# encoder-hbridge.net
KiCad netlist of a schematic drawn in EAGLE
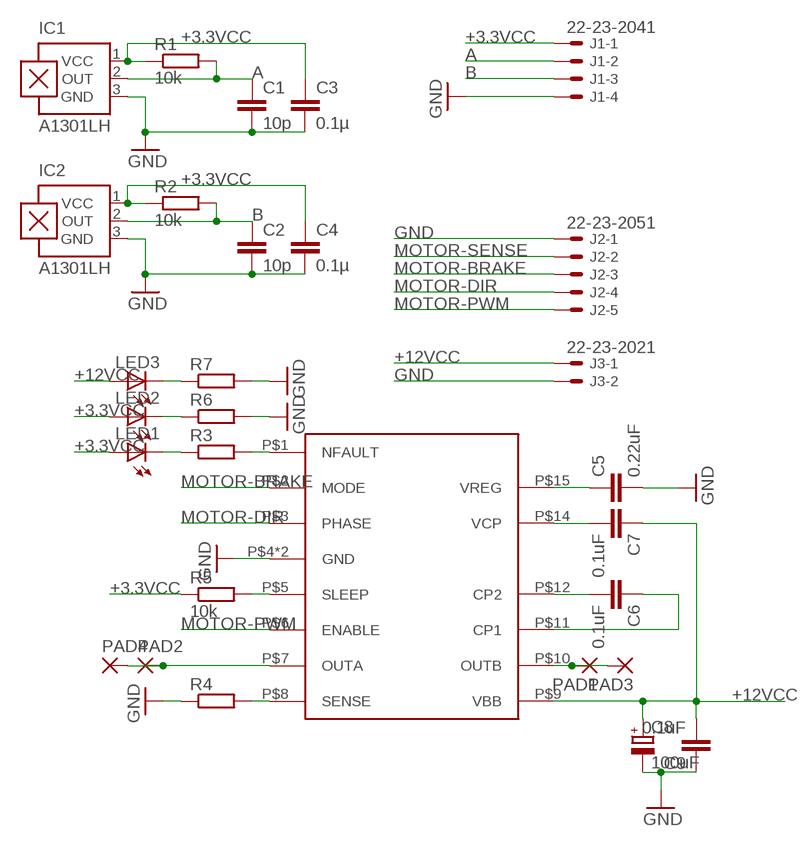
[diagram p0: schematic, sheet 1]

(export (version "E")
  (design (tool "Eeschema 10.0.6"))
  (components
    (comp (ref "C1")
      (value "10p")
      (footprint "eagle-import:C0805")
      (libsource (lib "eagle-import") (part "C-EUC0805"))
    )
    (comp (ref "C2")
      (value "10p")
      (footprint "eagle-import:C0805")
      (libsource (lib "eagle-import") (part "C-EUC0805"))
    )
    (comp (ref "C3")
      (value "0.1µ")
      (footprint "eagle-import:C0805")
      (libsource (lib "eagle-import") (part "C-EUC0805"))
    )
    (comp (ref "C4")
      (value "0.1µ")
      (footprint "eagle-import:C0805")
      (libsource (lib "eagle-import") (part "C-EUC0805"))
    )
    (comp (ref "C5")
      (value "0.22uF")
      (footprint "eagle-import:C0805")
      (libsource (lib "eagle-import") (part "C-EUC0805"))
    )
    (comp (ref "C6")
      (value "0.1uF")
      (footprint "eagle-import:C0805")
      (libsource (lib "eagle-import") (part "C-EUC0805"))
    )
    (comp (ref "C7")
      (value "0.1uF")
      (footprint "eagle-import:C0805")
      (libsource (lib "eagle-import") (part "C-EUC0805"))
    )
    (comp (ref "C8")
      (value "100uF")
      (footprint "eagle-import:E3,5-8")
      (libsource (lib "eagle-import") (part "CPOL-EUE3.5-8"))
    )
    (comp (ref "C9")
      (value "0.1uF")
      (footprint "eagle-import:C0805")
      (libsource (lib "eagle-import") (part "C-EUC0805"))
    )
    (comp (ref "IC1")
      (value "A1301LH")
      (footprint "eagle-import:SOT23-W")
      (fields (field (name "MF") "ALLEGRO MICROSYSTEMS, INC.") (field (name "MPN") "A1301ELHLT-T"))
      (libsource (lib "eagle-import") (part "A13?LH01"))
    )
    (comp (ref "IC2")
      (value "A1301LH")
      (footprint "eagle-import:SOT23-W")
      (fields (field (name "MF") "ALLEGRO MICROSYSTEMS, INC.") (field (name "MPN") "A1301ELHLT-T"))
      (libsource (lib "eagle-import") (part "A13?LH01"))
    )
    (comp (ref "J1")
      (value "22-23-2041")
      (footprint "eagle-import:22-23-2041")
      (fields (field (name "MF") "MOLEX"))
      (libsource (lib "eagle-import") (part "22-23-2041"))
    )
    (comp (ref "J2")
      (value "22-23-2051")
      (footprint "eagle-import:22-23-2051")
      (fields (field (name "MF") "MOLEX"))
      (libsource (lib "eagle-import") (part "22-23-2051"))
    )
    (comp (ref "J3")
      (value "22-23-2021")
      (footprint "eagle-import:22-23-2021")
      (fields (field (name "MF") "MOLEX"))
      (libsource (lib "eagle-import") (part "22-23-2021"))
    )
    (comp (ref "LED1")
      (value "LED3MM")
      (footprint "eagle-import:LED3MM")
      (libsource (lib "eagle-import") (part "LED3MM"))
    )
    (comp (ref "LED2")
      (value "LED3MM")
      (footprint "eagle-import:LED3MM")
      (libsource (lib "eagle-import") (part "LED3MM"))
    )
    (comp (ref "LED3")
      (value "LED3MM")
      (footprint "eagle-import:LED3MM")
      (libsource (lib "eagle-import") (part "LED3MM"))
    )
    (comp (ref "PAD1")
      (value "3,81/1,4")
      (footprint "eagle-import:3,81_1,4")
      (libsource (lib "eagle-import") (part "3,81/1,4"))
    )
    (comp (ref "PAD2")
      (value "3,81/1,4")
      (footprint "eagle-import:3,81_1,4")
      (libsource (lib "eagle-import") (part "3,81/1,4"))
    )
    (comp (ref "PAD3")
      (value "3,81/1,4")
      (footprint "eagle-import:3,81_1,4")
      (libsource (lib "eagle-import") (part "3,81/1,4"))
    )
    (comp (ref "PAD4")
      (value "3,81/1,4")
      (footprint "eagle-import:3,81_1,4")
      (libsource (lib "eagle-import") (part "3,81/1,4"))
    )
    (comp (ref "R1")
      (value "10k")
      (footprint "eagle-import:R0805")
      (libsource (lib "eagle-import") (part "R-EU_R0805"))
    )
    (comp (ref "R2")
      (value "10k")
      (footprint "eagle-import:R0805")
      (libsource (lib "eagle-import") (part "R-EU_R0805"))
    )
    (comp (ref "R3")
      (value "R-EU_R0805")
      (footprint "eagle-import:R0805")
      (libsource (lib "eagle-import") (part "R-EU_R0805"))
    )
    (comp (ref "R4")
      (value "R-EU_R0805")
      (footprint "eagle-import:R0805")
      (libsource (lib "eagle-import") (part "R-EU_R0805"))
    )
    (comp (ref "R5")
      (value "10k")
      (footprint "eagle-import:R0805")
      (libsource (lib "eagle-import") (part "R-EU_R0805"))
    )
    (comp (ref "R6")
      (value "R-EU_R0805")
      (footprint "eagle-import:R0805")
      (libsource (lib "eagle-import") (part "R-EU_R0805"))
    )
    (comp (ref "R7")
      (value "R-EU_R0805")
      (footprint "eagle-import:R0805")
      (libsource (lib "eagle-import") (part "R-EU_R0805"))
    )
    (comp (ref "U$1")
      (value "A3950-DIL")
      (footprint "eagle-import:DIL16")
      (libsource (lib "eagle-import") (part "A3950-DIL"))
    )
  )
  (nets
    (net (code "1") (name "/+3.3VCC") (class "Default")
      (node (ref "C3") (pin "1") (pinfunction "1_1") (pintype "passive"))
      (node (ref "C4") (pin "1") (pinfunction "1_1") (pintype "passive"))
      (node (ref "IC1") (pin "1") (pinfunction "VCC_1") (pintype "power_in"))
      (node (ref "IC2") (pin "1") (pinfunction "VCC_1") (pintype "power_in"))
      (node (ref "J1") (pin "1") (pinfunction "S_1") (pintype "passive"))
      (node (ref "LED1") (pin "A") (pinfunction "A_A") (pintype "passive"))
      (node (ref "LED2") (pin "A") (pinfunction "A_A") (pintype "passive"))
      (node (ref "R1") (pin "1") (pinfunction "1_1") (pintype "passive"))
      (node (ref "R2") (pin "1") (pinfunction "1_1") (pintype "passive"))
      (node (ref "R5") (pin "1") (pinfunction "1_1") (pintype "passive"))
    )
    (net (code "2") (name "/+12VCC") (class "Default")
      (node (ref "C7") (pin "1") (pinfunction "1_1") (pintype "passive"))
      (node (ref "C8") (pin "+") (pinfunction "+_+") (pintype "passive"))
      (node (ref "C9") (pin "2") (pinfunction "2_2") (pintype "passive"))
      (node (ref "J3") (pin "1") (pinfunction "S_1") (pintype "passive"))
      (node (ref "LED3") (pin "A") (pinfunction "A_A") (pintype "passive"))
      (node (ref "U$1") (pin "P$9") (pinfunction "VBB_P$9") (pintype "bidirectional"))
    )
    (net (code "3") (name "/A") (class "Default")
      (node (ref "C1") (pin "1") (pinfunction "1_1") (pintype "passive"))
      (node (ref "IC1") (pin "2") (pinfunction "OUT_2") (pintype "output"))
      (node (ref "J1") (pin "2") (pinfunction "S_2") (pintype "passive"))
      (node (ref "R1") (pin "2") (pinfunction "2_2") (pintype "passive"))
    )
    (net (code "4") (name "/B") (class "Default")
      (node (ref "C2") (pin "1") (pinfunction "1_1") (pintype "passive"))
      (node (ref "IC2") (pin "2") (pinfunction "OUT_2") (pintype "output"))
      (node (ref "J1") (pin "3") (pinfunction "S_3") (pintype "passive"))
      (node (ref "R2") (pin "2") (pinfunction "2_2") (pintype "passive"))
    )
    (net (code "5") (name "/MOTOR-BRAKE") (class "Default")
      (node (ref "J2") (pin "3") (pinfunction "S_3") (pintype "passive"))
      (node (ref "U$1") (pin "P$2") (pinfunction "MODE_P$2") (pintype "bidirectional"))
    )
    (net (code "6") (name "/MOTOR-DIR") (class "Default")
      (node (ref "J2") (pin "4") (pinfunction "S_4") (pintype "passive"))
      (node (ref "U$1") (pin "P$3") (pinfunction "PHASE_P$3") (pintype "bidirectional"))
    )
    (net (code "7") (name "/MOTOR-PWM") (class "Default")
      (node (ref "J2") (pin "5") (pinfunction "S_5") (pintype "passive"))
      (node (ref "U$1") (pin "P$6") (pinfunction "ENABLE_P$6") (pintype "bidirectional"))
    )
    (net (code "8") (name "/MOTOR-SENSE") (class "Default")
      (node (ref "J2") (pin "2") (pinfunction "S_2") (pintype "passive"))
    )
    (net (code "9") (name "GND") (class "Default")
      (node (ref "C1") (pin "2") (pinfunction "2_2") (pintype "passive"))
      (node (ref "C2") (pin "2") (pinfunction "2_2") (pintype "passive"))
      (node (ref "C3") (pin "2") (pinfunction "2_2") (pintype "passive"))
      (node (ref "C4") (pin "2") (pinfunction "2_2") (pintype "passive"))
      (node (ref "C5") (pin "2") (pinfunction "2_2") (pintype "passive"))
      (node (ref "C8") (pin "-") (pinfunction "-_-") (pintype "passive"))
      (node (ref "C9") (pin "1") (pinfunction "1_1") (pintype "passive"))
      (node (ref "IC1") (pin "3") (pinfunction "GND_3") (pintype "power_in"))
      (node (ref "IC2") (pin "3") (pinfunction "GND_3") (pintype "power_in"))
      (node (ref "J1") (pin "4") (pinfunction "S_4") (pintype "passive"))
      (node (ref "J2") (pin "1") (pinfunction "S_1") (pintype "passive"))
      (node (ref "J3") (pin "2") (pinfunction "S_2") (pintype "passive"))
      (node (ref "R4") (pin "1") (pinfunction "1_1") (pintype "passive"))
      (node (ref "R6") (pin "2") (pinfunction "2_2") (pintype "passive"))
      (node (ref "R7") (pin "2") (pinfunction "2_2") (pintype "passive"))
      (node (ref "U$1") (pin "P$13") (pinfunction "GND_P$13") (pintype "bidirectional"))
      (node (ref "U$1") (pin "P$4") (pinfunction "GND_P$4") (pintype "bidirectional"))
    )
    (net (code "10") (name "Net-(LED1-C)") (class "Default")
      (node (ref "LED1") (pin "K") (pinfunction "C_K") (pintype "passive"))
      (node (ref "R3") (pin "1") (pinfunction "1_1") (pintype "passive"))
    )
    (net (code "11") (name "Net-(LED2-C)") (class "Default")
      (node (ref "LED2") (pin "K") (pinfunction "C_K") (pintype "passive"))
      (node (ref "R6") (pin "1") (pinfunction "1_1") (pintype "passive"))
    )
    (net (code "12") (name "Net-(LED3-C)") (class "Default")
      (node (ref "LED3") (pin "K") (pinfunction "C_K") (pintype "passive"))
      (node (ref "R7") (pin "1") (pinfunction "1_1") (pintype "passive"))
    )
    (net (code "13") (name "Net-(PAD1-P)") (class "Default")
      (node (ref "PAD1") (pin "1") (pinfunction "P_1") (pintype "passive"))
      (node (ref "PAD3") (pin "1") (pinfunction "P_1") (pintype "passive"))
      (node (ref "U$1") (pin "P$10") (pinfunction "OUTB_P$10") (pintype "bidirectional"))
    )
    (net (code "14") (name "Net-(PAD2-P)") (class "Default")
      (node (ref "PAD2") (pin "1") (pinfunction "P_1") (pintype "passive"))
      (node (ref "PAD4") (pin "1") (pinfunction "P_1") (pintype "passive"))
      (node (ref "U$1") (pin "P$7") (pinfunction "OUTA_P$7") (pintype "bidirectional"))
    )
    (net (code "15") (name "Net-(U$1-CP1)") (class "Default")
      (node (ref "C6") (pin "1") (pinfunction "1_1") (pintype "passive"))
      (node (ref "U$1") (pin "P$11") (pinfunction "CP1_P$11") (pintype "bidirectional"))
    )
    (net (code "16") (name "Net-(U$1-CP2)") (class "Default")
      (node (ref "C6") (pin "2") (pinfunction "2_2") (pintype "passive"))
      (node (ref "U$1") (pin "P$12") (pinfunction "CP2_P$12") (pintype "bidirectional"))
    )
    (net (code "17") (name "Net-(U$1-NFAULT)") (class "Default")
      (node (ref "R3") (pin "2") (pinfunction "2_2") (pintype "passive"))
      (node (ref "U$1") (pin "P$1") (pinfunction "NFAULT_P$1") (pintype "bidirectional"))
    )
    (net (code "18") (name "Net-(U$1-SENSE)") (class "Default")
      (node (ref "R4") (pin "2") (pinfunction "2_2") (pintype "passive"))
      (node (ref "U$1") (pin "P$8") (pinfunction "SENSE_P$8") (pintype "bidirectional"))
    )
    (net (code "19") (name "Net-(U$1-SLEEP)") (class "Default")
      (node (ref "R5") (pin "2") (pinfunction "2_2") (pintype "passive"))
      (node (ref "U$1") (pin "P$5") (pinfunction "SLEEP_P$5") (pintype "bidirectional"))
    )
    (net (code "20") (name "Net-(U$1-VCP)") (class "Default")
      (node (ref "C7") (pin "2") (pinfunction "2_2") (pintype "passive"))
      (node (ref "U$1") (pin "P$14") (pinfunction "VCP_P$14") (pintype "bidirectional"))
    )
    (net (code "21") (name "Net-(U$1-VREG)") (class "Default")
      (node (ref "C5") (pin "1") (pinfunction "1_1") (pintype "passive"))
      (node (ref "U$1") (pin "P$15") (pinfunction "VREG_P$15") (pintype "bidirectional"))
    )
  )
)
